# Motor_Interface_-_CAN.net
KiCad netlist of a schematic drawn in Altium Designer
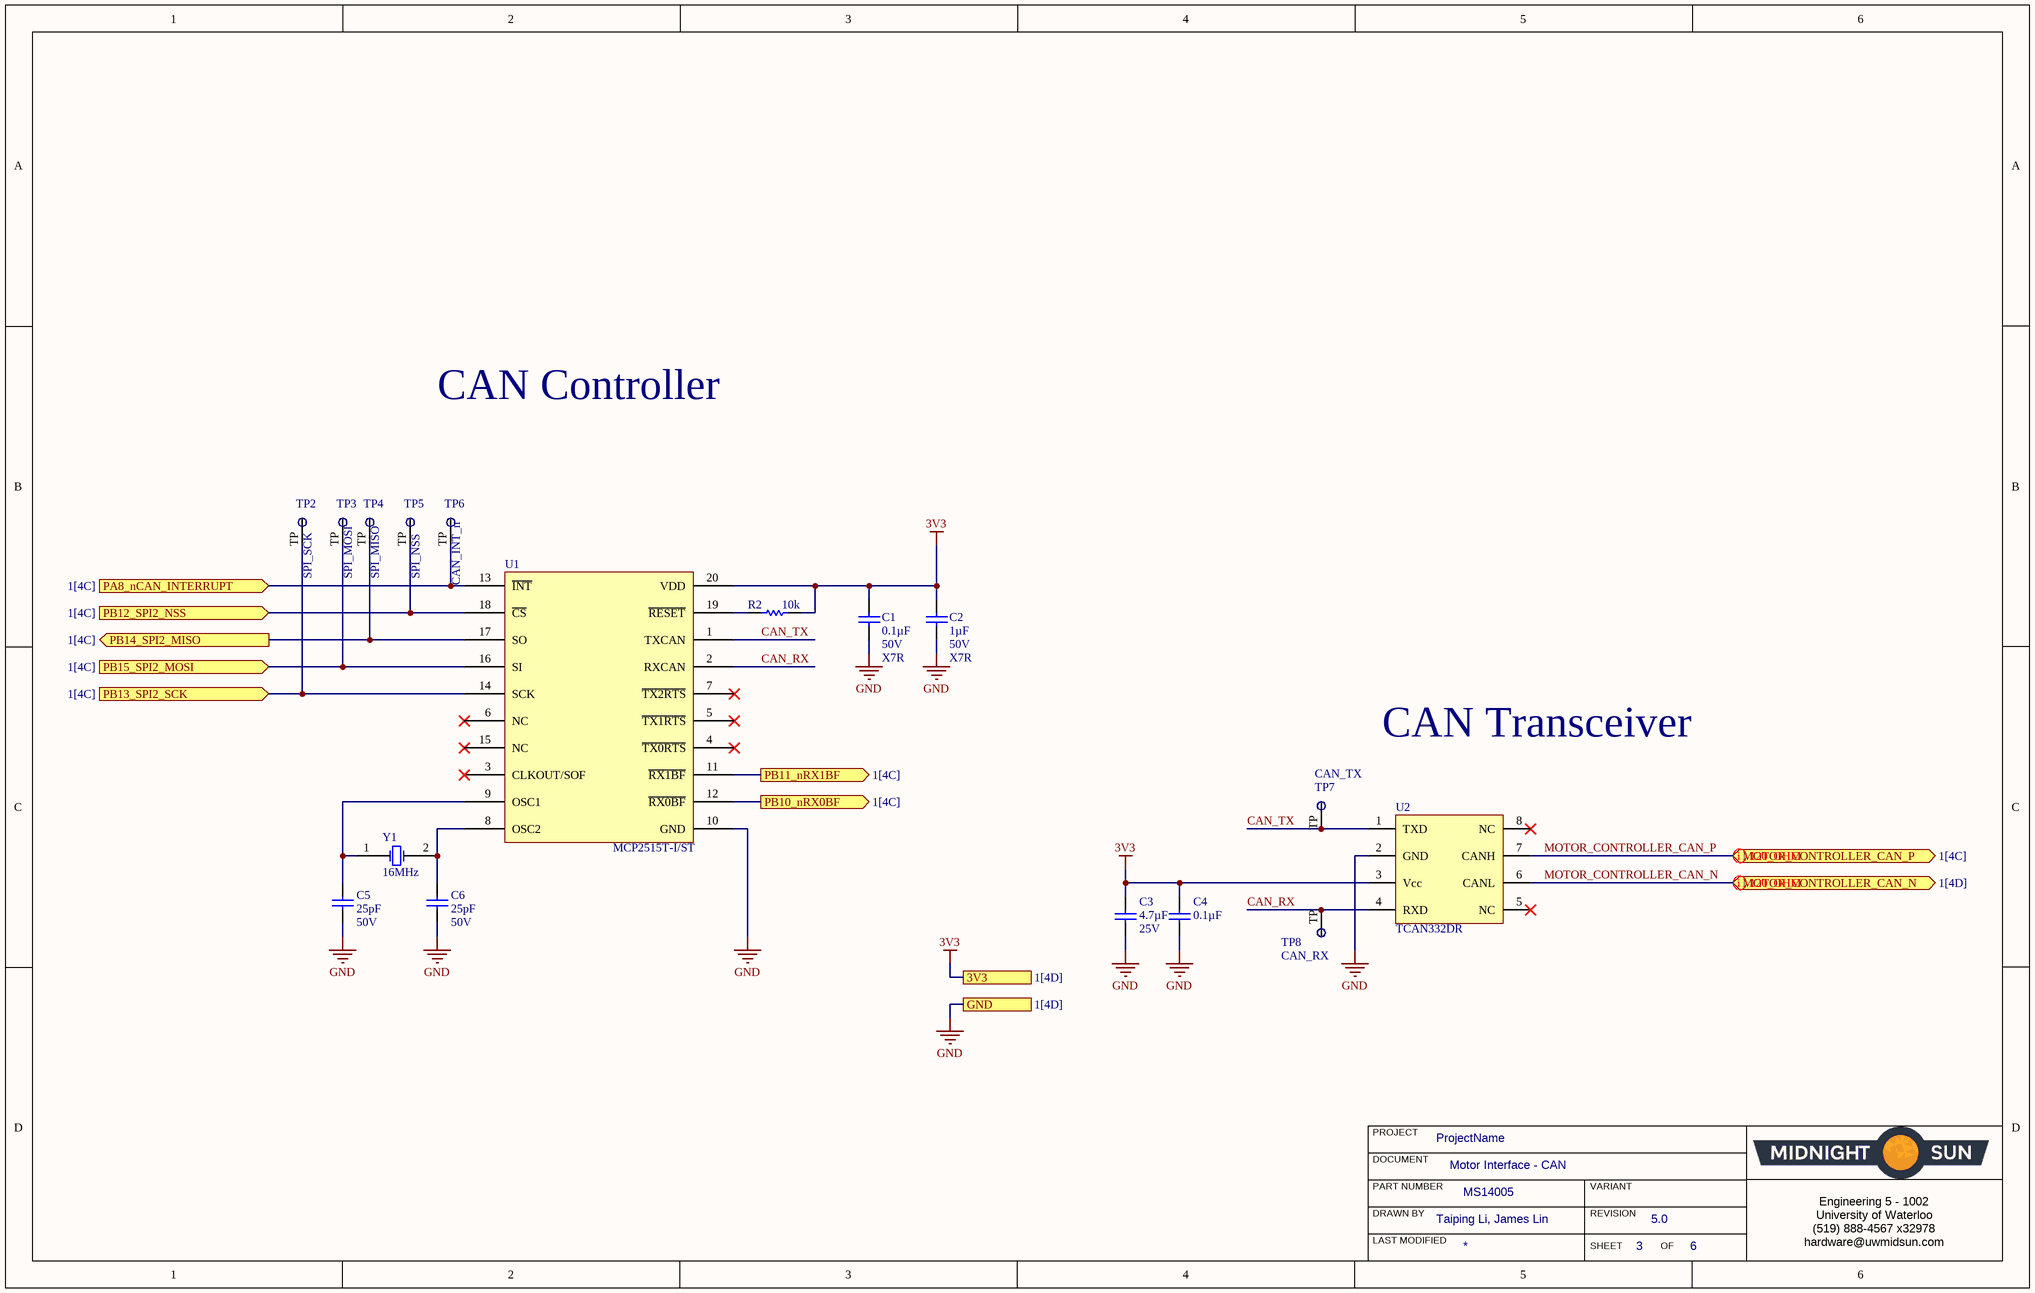
[diagram p0: Motor Interface - CAN.SchDoc]

(export (version "E")
  (design (tool "Eeschema 10.0.6"))
  (components
    (comp (ref "C1")
      (value "CAP CER 0.1UF 50V 10% X7R 0603")
      (footprint "CAP, 0603")
      (description "0.10µF ±10% 50V Ceramic Capacitor X7R 0603 (1608 Metric)")
      (fields
        (field (name "TOLERANCE") "±10%")
        (field (name "CAPACITANCE") "0.1µF")
        (field (name "VOLTAGE") "50V")
        (field (name "TEMPERATURE COEFFICIENT") "X7R")
      )
      (libsource (lib "Schematic Diagrams") (part "CAP CER 0.1UF 50V 10% X7R 0603"))
    )
    (comp (ref "C2")
      (value "CAP CER 1UF 50V 10% X7R 0603")
      (footprint "CAP, 0603")
      (description "1µF ±10% 50V Ceramic Capacitor X7R 0603 (1608 Metric)")
      (fields
        (field (name "TOLERANCE") "±10%")
        (field (name "CAPACITANCE") "1µF")
        (field (name "VOLTAGE") "50V")
        (field (name "TEMPERATURE COEFFICIENT") "X7R")
      )
      (libsource (lib "Schematic Diagrams") (part "CAP CER 1UF 50V 10% X7R 0603"))
    )
    (comp (ref "C3")
      (value "CAP CER 4.7UF 25V 10% X5R 0603")
      (footprint "CAP, 0603")
      (description "4.7µF ±10% 25V Ceramic Capacitor X5R 0603 (1608 Metric)")
      (fields
        (field (name "VOLTAGE") "25V")
        (field (name "TOLERANCE") "±10%")
        (field (name "CAPACITANCE") "4.7µF")
      )
      (libsource (lib "Schematic Diagrams") (part "CAP CER 4.7UF 25V 10% X5R 0603"))
    )
    (comp (ref "C4")
      (value "CAP CER 0.1UF 50V 10% X7R 0603")
      (footprint "CAP, 0603")
      (description "0.10µF ±10% 50V Ceramic Capacitor X7R 0603 (1608 Metric)")
      (fields
        (field (name "VOLTAGE") "50V")
        (field (name "TOLERANCE") "±10%")
        (field (name "CAPACITANCE") "0.1µF")
      )
      (libsource (lib "Schematic Diagrams") (part "CAP CER 0.1UF 50V 10% X7R 0603"))
    )
    (comp (ref "C5")
      (value "CAP CER 25PF 50V ±5% C0G/NP0 0603")
      (footprint "CAP, 0603")
      (description "25pF 50V Ceramic Capacitor C0G, NP0 0603 (1608 Metric) 0.063\" L x 0.032\" W (1.60mm x 0.80mm)")
      (fields
        (field (name "MANUFACTURER") "Samsung Electro-Mechanics")
        (field (name "MANUFACTURER PART NUMBER") "CL10C250JB8NNNC")
        (field (name "VOLTAGE - RATED") "50V")
        (field (name "CAPACITANCE") "25pF")
      )
      (libsource (lib "Schematic Diagrams") (part "CAP CER 25PF 50V ±5% C0G/NP0 0603"))
    )
    (comp (ref "C6")
      (value "CAP CER 25PF 50V ±5% C0G/NP0 0603")
      (footprint "CAP, 0603")
      (description "25pF 50V Ceramic Capacitor C0G, NP0 0603 (1608 Metric) 0.063\" L x 0.032\" W (1.60mm x 0.80mm)")
      (fields
        (field (name "MANUFACTURER") "Samsung Electro-Mechanics")
        (field (name "MANUFACTURER PART NUMBER") "CL10C250JB8NNNC")
        (field (name "VOLTAGE - RATED") "50V")
        (field (name "CAPACITANCE") "25pF")
      )
      (libsource (lib "Schematic Diagrams") (part "CAP CER 25PF 50V ±5% C0G/NP0 0603"))
    )
    (comp (ref "R2")
      (value "RES 10K OHM 1% 1/10W 0603")
      (footprint "RES, 0603")
      (description "RES SMD 10K OHM 1% 1/10W 0603")
      (fields
        (field (name "TOLERANCE") "±1%")
        (field (name "RESISTANCE") "10k")
        (field (name "POWER") "1/10W")
      )
      (libsource (lib "Schematic Diagrams") (part "RES 10K OHM 1% 1/10W 0603"))
    )
    (comp (ref "TP2")
      (value "SPI_SCK")
      (footprint "Test Point")
      (libsource (lib "Schematic Diagrams") (part "Test Point"))
    )
    (comp (ref "TP3")
      (value "SPI_MOSI")
      (footprint "Test Point")
      (libsource (lib "Schematic Diagrams") (part "Test Point"))
    )
    (comp (ref "TP4")
      (value "SPI_MISO")
      (footprint "Test Point")
      (libsource (lib "Schematic Diagrams") (part "Test Point"))
    )
    (comp (ref "TP5")
      (value "SPI_NSS")
      (footprint "Test Point")
      (libsource (lib "Schematic Diagrams") (part "Test Point"))
    )
    (comp (ref "TP6")
      (value "CAN_INT_n")
      (footprint "Test Point")
      (libsource (lib "Schematic Diagrams") (part "Test Point"))
    )
    (comp (ref "TP7")
      (value "CAN_TX")
      (footprint "Test Point")
      (libsource (lib "Schematic Diagrams") (part "Test Point"))
    )
    (comp (ref "TP8")
      (value "CAN_RX")
      (footprint "Test Point")
      (libsource (lib "Schematic Diagrams") (part "Test Point"))
    )
    (comp (ref "U1")
      (value "MCP2515")
      (footprint "TSSOP65P640X120-20N")
      (description "CAN Controller CAN 2.0 SPI Interface 20-TSSOP")
      (fields
        (field (name "MANUFACTURER") "Microchip Technology")
        (field (name "MANUFACTURER PART NUMBER") "MCP2515T-I/ST")
      )
      (libsource (lib "altium-import") (part "root_0_IC CAN SPI CONTROLLER MCP2515T-I/ST 20-TSSOP_"))
    )
    (comp (ref "U2")
      (value "IC CAN Tranceiver TCAN332DR")
      (footprint "TSOP65P280X145-8N")
      (description "1/1 Transceiver CAN 8-SOIC")
      (fields
        (field (name "MANUFACTURER PART NUMBER") "TCAN332DR")
        (field (name "DIGIKEY PART NUMBER") "296-43711-1-ND")
      )
      (libsource (lib "Schematic Diagrams") (part "IC CAN Tranceiver TCAN332DR"))
    )
    (comp (ref "Y1")
      (value "CRYSTAL 16 MHz 18PF 2-SMD")
      (footprint "ABM3 CRYSTAL")
      (description "16MHz ±20ppm Crystal 18pF 40 Ohms 2-SMD, No Lead")
      (fields
        (field (name "MANUFACTURER") "Abracon LLC")
        (field (name "MANUFACTURER PART NUMBER") "ABM3-16.000MHZ-D2Y-T")
        (field (name "FREQUENCY") "16MHz")
      )
      (libsource (lib "Schematic Diagrams") (part "CRYSTAL 16 MHz 18PF 2-SMD"))
    )
  )
  (nets
    (net (code "1") (name "/CAN_RX") (class "Default")
      (node (ref "TP8") (pin "TP") (pinfunction "1_TP") (pintype "passive"))
      (node (ref "U1") (pin "2") (pinfunction "RXCAN_2") (pintype "passive"))
      (node (ref "U2") (pin "4") (pinfunction "RXD_4") (pintype "passive"))
    )
    (net (code "2") (name "/CAN_TX") (class "Default")
      (node (ref "TP7") (pin "TP") (pinfunction "1_TP") (pintype "passive"))
      (node (ref "U1") (pin "1") (pinfunction "TXCAN_1") (pintype "passive"))
      (node (ref "U2") (pin "1") (pinfunction "TXD_1") (pintype "passive"))
    )
    (net (code "3") (name "/MOTOR_CONTROLLER_CAN_N") (class "Default")
      (node (ref "U2") (pin "6") (pinfunction "CANL_6") (pintype "passive"))
    )
    (net (code "4") (name "/MOTOR_CONTROLLER_CAN_P") (class "Default")
      (node (ref "U2") (pin "7") (pinfunction "CANH_7") (pintype "passive"))
    )
    (net (code "5") (name "/PA8_nCAN_INTERRUPT") (class "Default")
      (node (ref "TP6") (pin "TP") (pinfunction "1_TP") (pintype "passive"))
      (node (ref "U1") (pin "13") (pinfunction "~{INT}_13") (pintype "passive"))
    )
    (net (code "6") (name "/PB10_nRX0BF") (class "Default")
      (node (ref "U1") (pin "12") (pinfunction "~{RX0BF}_12") (pintype "passive"))
    )
    (net (code "7") (name "/PB11_nRX1BF") (class "Default")
      (node (ref "U1") (pin "11") (pinfunction "~{RX1BF}_11") (pintype "passive"))
    )
    (net (code "8") (name "/PB12_SPI2_NSS") (class "Default")
      (node (ref "TP5") (pin "TP") (pinfunction "1_TP") (pintype "passive"))
      (node (ref "U1") (pin "18") (pinfunction "~{CS}_18") (pintype "passive"))
    )
    (net (code "9") (name "/PB13_SPI2_SCK") (class "Default")
      (node (ref "TP2") (pin "TP") (pinfunction "1_TP") (pintype "passive"))
      (node (ref "U1") (pin "14") (pinfunction "SCK_14") (pintype "passive"))
    )
    (net (code "10") (name "/PB14_SPI2_MISO") (class "Default")
      (node (ref "TP4") (pin "TP") (pinfunction "1_TP") (pintype "passive"))
      (node (ref "U1") (pin "17") (pinfunction "SO_17") (pintype "passive"))
    )
    (net (code "11") (name "/PB15_SPI2_MOSI") (class "Default")
      (node (ref "TP3") (pin "TP") (pinfunction "1_TP") (pintype "passive"))
      (node (ref "U1") (pin "16") (pinfunction "SI_16") (pintype "passive"))
    )
    (net (code "12") (name "3V3") (class "Default")
      (node (ref "C1") (pin "1") (pinfunction "1_1") (pintype "passive"))
      (node (ref "C2") (pin "1") (pinfunction "1_1") (pintype "passive"))
      (node (ref "C3") (pin "2") (pinfunction "2_2") (pintype "passive"))
      (node (ref "C4") (pin "2") (pinfunction "2_2") (pintype "passive"))
      (node (ref "R2") (pin "2") (pinfunction "2_2") (pintype "passive"))
      (node (ref "U1") (pin "20") (pinfunction "VDD_20") (pintype "passive"))
      (node (ref "U2") (pin "3") (pinfunction "Vcc_3") (pintype "passive"))
    )
    (net (code "13") (name "GND") (class "Default")
      (node (ref "C1") (pin "2") (pinfunction "2_2") (pintype "passive"))
      (node (ref "C2") (pin "2") (pinfunction "2_2") (pintype "passive"))
      (node (ref "C3") (pin "1") (pinfunction "1_1") (pintype "passive"))
      (node (ref "C4") (pin "1") (pinfunction "1_1") (pintype "passive"))
      (node (ref "C5") (pin "2") (pinfunction "2_2") (pintype "passive"))
      (node (ref "C6") (pin "2") (pinfunction "2_2") (pintype "passive"))
      (node (ref "U1") (pin "10") (pinfunction "GND_10") (pintype "passive"))
      (node (ref "U2") (pin "2") (pinfunction "GND_2") (pintype "passive"))
    )
    (net (code "14") (name "Net-(U1-OSC1)") (class "Default")
      (node (ref "C5") (pin "1") (pinfunction "1_1") (pintype "passive"))
      (node (ref "U1") (pin "9") (pinfunction "OSC1_9") (pintype "passive"))
      (node (ref "Y1") (pin "1") (pinfunction "1_1") (pintype "passive"))
    )
    (net (code "15") (name "Net-(U1-OSC2)") (class "Default")
      (node (ref "C6") (pin "1") (pinfunction "1_1") (pintype "passive"))
      (node (ref "U1") (pin "8") (pinfunction "OSC2_8") (pintype "passive"))
      (node (ref "Y1") (pin "2") (pinfunction "2_2") (pintype "passive"))
    )
    (net (code "16") (name "Net-(U1-~{RESET})") (class "Default")
      (node (ref "R2") (pin "1") (pinfunction "1_1") (pintype "passive"))
      (node (ref "U1") (pin "19") (pinfunction "~{RESET}_19") (pintype "passive"))
    )
    (net (code "17") (name "unconnected-(U1-CLKOUT{slash}SOF-Pad3)") (class "Default")
      (node (ref "U1") (pin "3") (pinfunction "CLKOUT/SOF_3") (pintype "passive+no_connect"))
    )
    (net (code "18") (name "unconnected-(U1-NC-Pad6)") (class "Default")
      (node (ref "U1") (pin "6") (pinfunction "NC_6") (pintype "passive+no_connect"))
    )
    (net (code "19") (name "unconnected-(U1-NC-Pad15)") (class "Default")
      (node (ref "U1") (pin "15") (pinfunction "NC_15") (pintype "passive+no_connect"))
    )
    (net (code "20") (name "unconnected-(U1-~{TX0RTS}-Pad4)") (class "Default")
      (node (ref "U1") (pin "4") (pinfunction "~{TX0RTS}_4") (pintype "passive+no_connect"))
    )
    (net (code "21") (name "unconnected-(U1-~{TX1RTS}-Pad5)") (class "Default")
      (node (ref "U1") (pin "5") (pinfunction "~{TX1RTS}_5") (pintype "passive+no_connect"))
    )
    (net (code "22") (name "unconnected-(U1-~{TX2RTS}-Pad7)") (class "Default")
      (node (ref "U1") (pin "7") (pinfunction "~{TX2RTS}_7") (pintype "passive+no_connect"))
    )
    (net (code "23") (name "unconnected-(U2-NC-Pad5)") (class "Default")
      (node (ref "U2") (pin "5") (pinfunction "NC_5") (pintype "passive+no_connect"))
    )
    (net (code "24") (name "unconnected-(U2-NC-Pad8)") (class "Default")
      (node (ref "U2") (pin "8") (pinfunction "NC_8") (pintype "passive+no_connect"))
    )
  )
)
